# lora_external_dev_board.net
KiCad netlist of a schematic drawn in EasyEDA
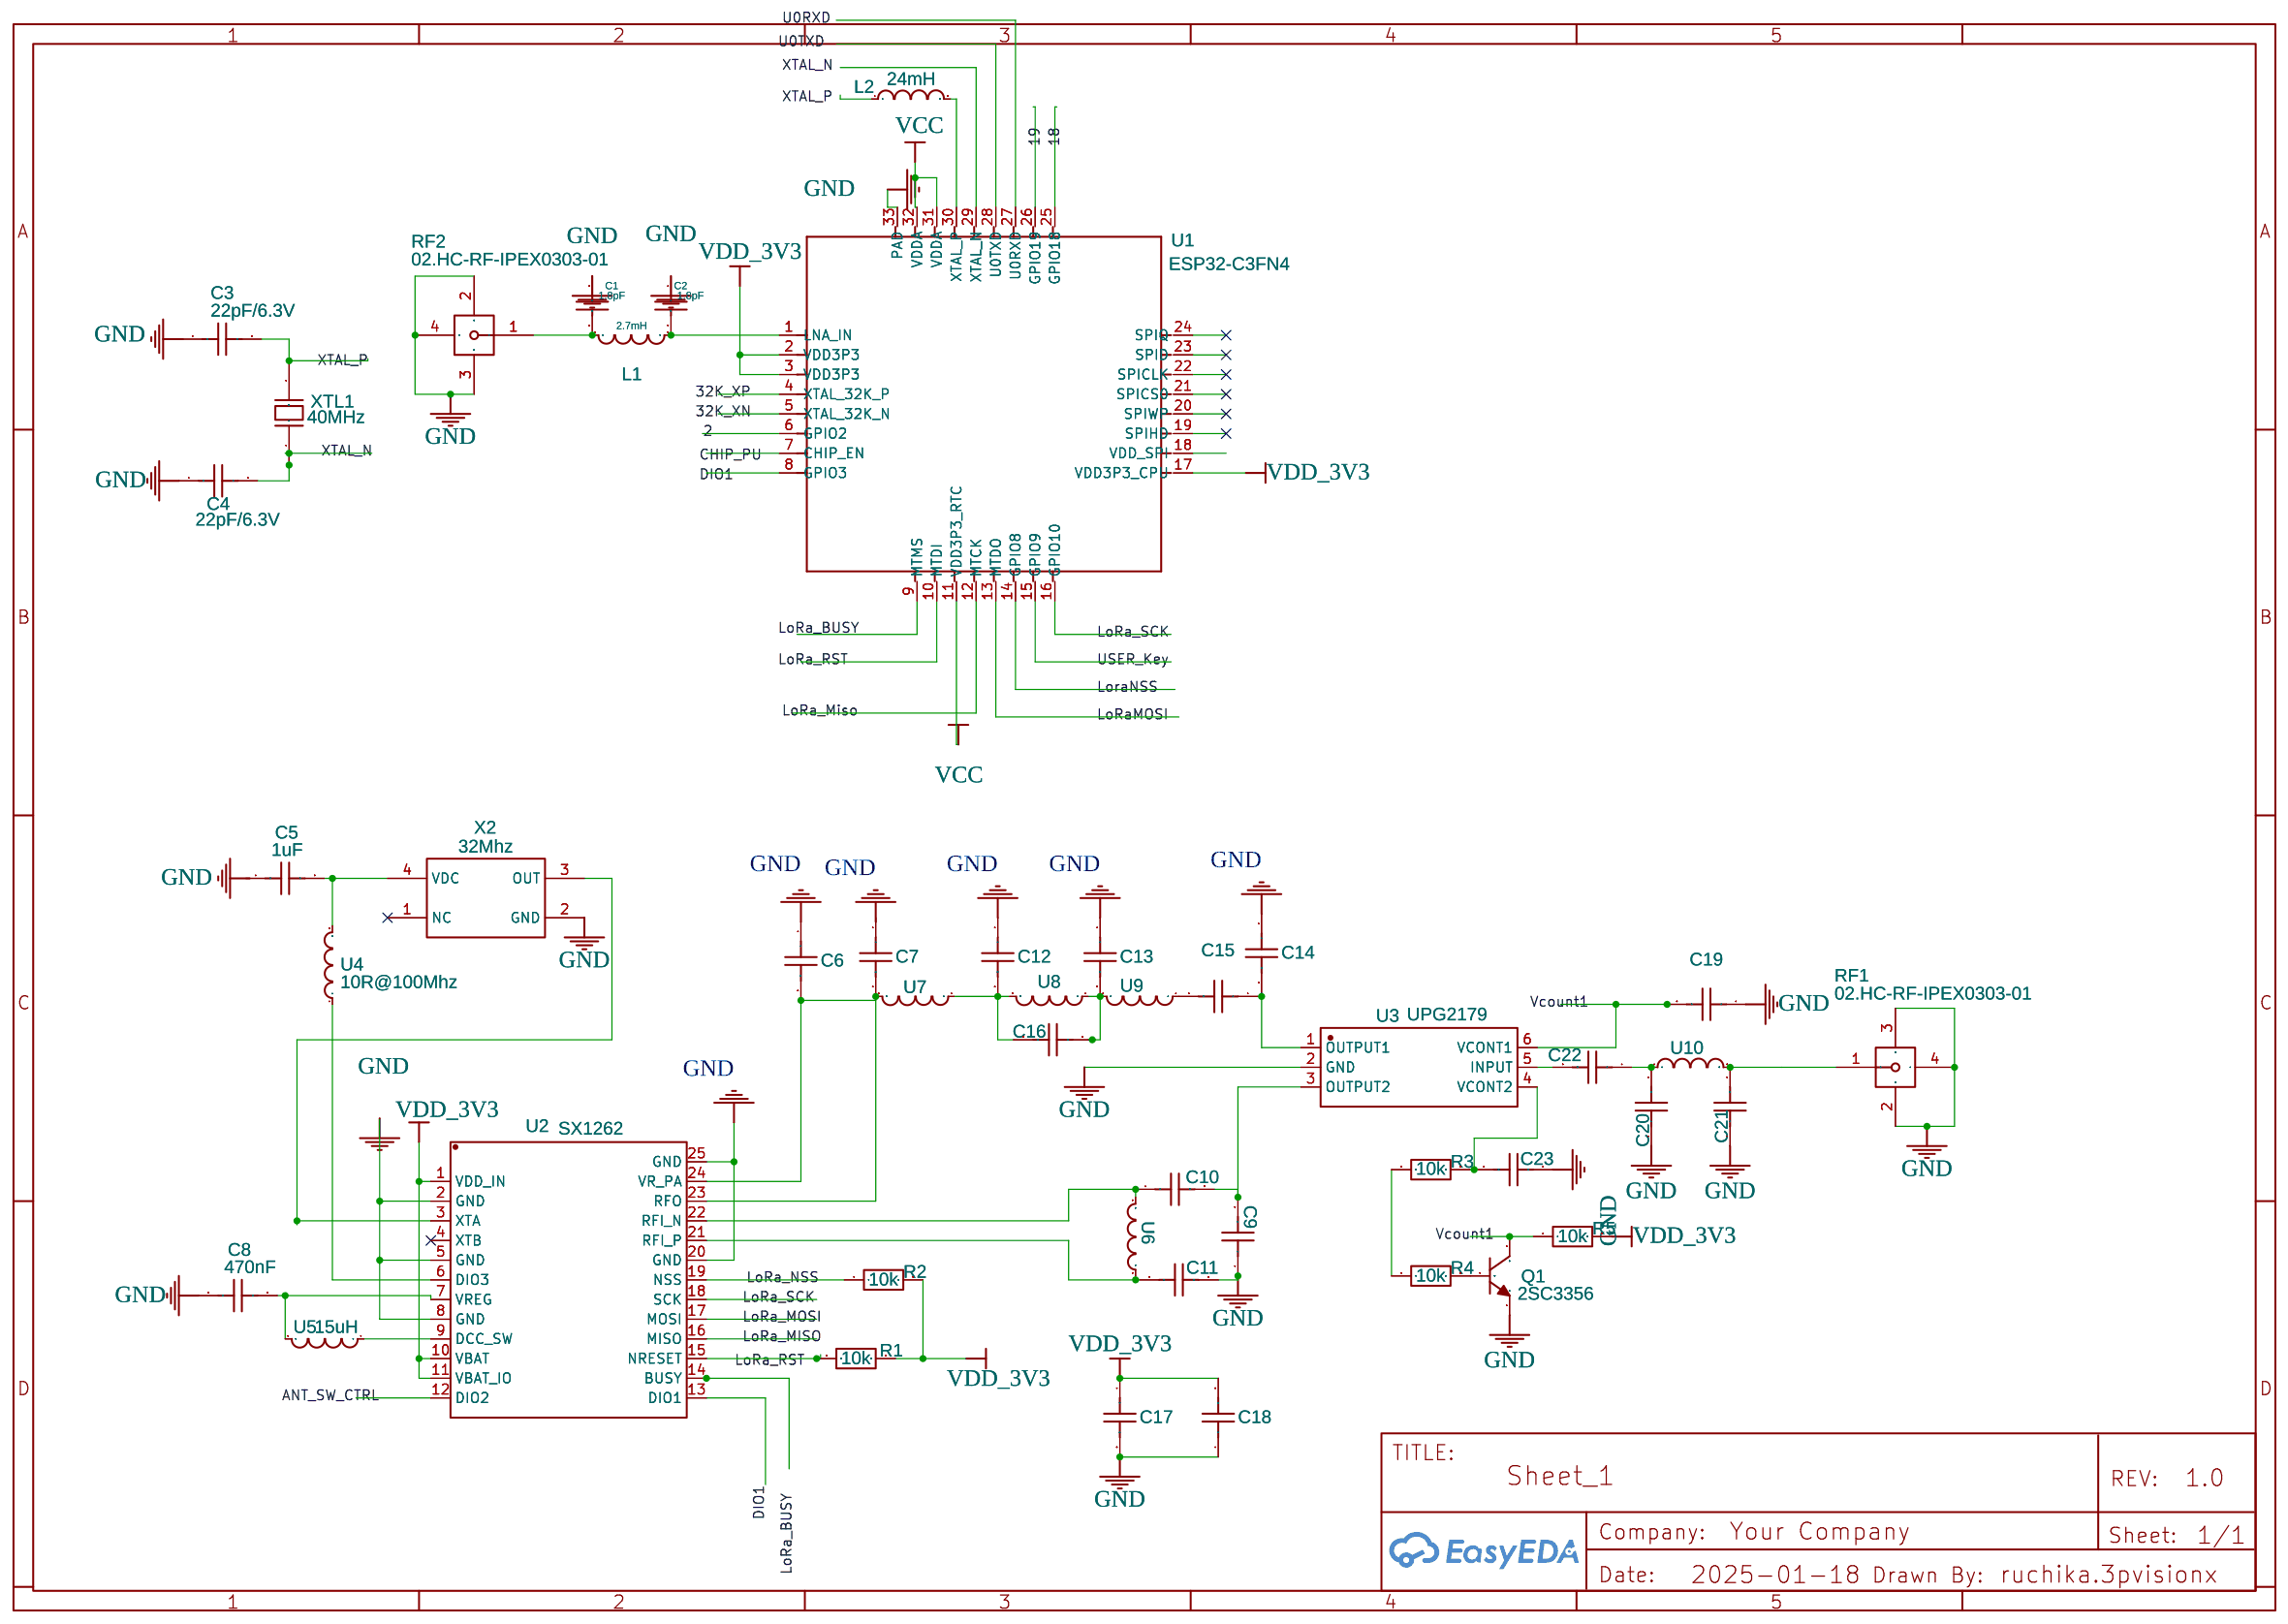
[diagram p0: schematic sheet]

(export (version "E")
  (design (tool "Eeschema 10.0.6"))
  (components
    (comp (ref "C1")
      (value "1.8pF")
      (fields
        (field (name "Manufacturer Part") "GJM1555C1H1R8BB01D")
        (field (name "Manufacturer") "muRata(村田)")
      )
      (libsource (lib "") (part "GJM1555C1H1R8BB01D"))
    )
    (comp (ref "C2")
      (value "1.8pF")
      (fields
        (field (name "Manufacturer Part") "GJM1555C1H1R8BB01D")
        (field (name "Manufacturer") "muRata(村田)")
      )
      (libsource (lib "") (part "GJM1555C1H1R8BB01D"))
    )
    (comp (ref "C3")
      (value "22pF/6.3V")
      (fields (field (name "Manufacturer Part") "22pF/6.3V(10%)-0402"))
      (libsource (lib "") (part "22PF/6.3V(10%)-0402"))
    )
    (comp (ref "C4")
      (value "22pF/6.3V")
      (fields (field (name "Manufacturer Part") "22pF/6.3V(10%)-0402"))
      (libsource (lib "") (part "22PF/6.3V(10%)-0402"))
    )
    (comp (ref "C5")
      (value "1uF")
      (fields
        (field (name "Manufacturer Part") "1uf/250V/CBBCapacitor")
        (field (name "Manufacturer") "ReliaPro")
      )
      (libsource (lib "") (part "1uf/250V/CBBCapacitor_2"))
    )
    (comp (ref "C6")
      (value "1uF")
      (fields
        (field (name "Manufacturer Part") "1uf/250V/CBBCapacitor")
        (field (name "Manufacturer") "ReliaPro")
      )
      (libsource (lib "") (part "1uf/250V/CBBCapacitor"))
    )
    (comp (ref "C7")
      (value "1uF")
      (fields
        (field (name "Manufacturer Part") "1uf/250V/CBBCapacitor")
        (field (name "Manufacturer") "ReliaPro")
      )
      (libsource (lib "") (part "1uf/250V/CBBCapacitor"))
    )
    (comp (ref "C8")
      (value "470nF")
      (fields
        (field (name "Manufacturer Part") "1uf/250V/CBBCapacitor")
        (field (name "Manufacturer") "ReliaPro")
      )
      (libsource (lib "") (part "1uf/250V/CBBCapacitor_2"))
    )
    (comp (ref "C9")
      (value "1uF")
      (fields
        (field (name "Manufacturer Part") "1uf/250V/CBBCapacitor")
        (field (name "Manufacturer") "ReliaPro")
      )
      (libsource (lib "") (part "1uf/250V/CBBCapacitor_1"))
    )
    (comp (ref "C10")
      (value "1uF")
      (fields
        (field (name "Manufacturer Part") "1uf/250V/CBBCapacitor")
        (field (name "Manufacturer") "ReliaPro")
      )
      (libsource (lib "") (part "1uf/250V/CBBCapacitor_2"))
    )
    (comp (ref "C11")
      (value "1uF")
      (fields
        (field (name "Manufacturer Part") "1uf/250V/CBBCapacitor")
        (field (name "Manufacturer") "ReliaPro")
      )
      (libsource (lib "") (part "1uf/250V/CBBCapacitor_2"))
    )
    (comp (ref "C12")
      (value "1uF")
      (fields
        (field (name "Manufacturer Part") "1uf/250V/CBBCapacitor")
        (field (name "Manufacturer") "ReliaPro")
      )
      (libsource (lib "") (part "1uf/250V/CBBCapacitor"))
    )
    (comp (ref "C13")
      (value "1uF")
      (fields
        (field (name "Manufacturer Part") "1uf/250V/CBBCapacitor")
        (field (name "Manufacturer") "ReliaPro")
      )
      (libsource (lib "") (part "1uf/250V/CBBCapacitor"))
    )
    (comp (ref "C14")
      (value "1uF")
      (fields
        (field (name "Manufacturer Part") "1uf/250V/CBBCapacitor")
        (field (name "Manufacturer") "ReliaPro")
      )
      (libsource (lib "") (part "1uf/250V/CBBCapacitor"))
    )
    (comp (ref "C15")
      (value "1uF")
      (fields
        (field (name "Manufacturer Part") "1uf/250V/CBBCapacitor")
        (field (name "Manufacturer") "ReliaPro")
      )
      (libsource (lib "") (part "1uf/250V/CBBCapacitor_3"))
    )
    (comp (ref "C16")
      (value "1uF")
      (fields
        (field (name "Manufacturer Part") "1uf/250V/CBBCapacitor")
        (field (name "Manufacturer") "ReliaPro")
      )
      (libsource (lib "") (part "1uf/250V/CBBCapacitor_3"))
    )
    (comp (ref "C17")
      (value "1uF")
      (fields
        (field (name "Manufacturer Part") "1uf/250V/CBBCapacitor")
        (field (name "Manufacturer") "ReliaPro")
      )
      (libsource (lib "") (part "1uf/250V/CBBCapacitor"))
    )
    (comp (ref "C18")
      (value "1uF")
      (fields
        (field (name "Manufacturer Part") "1uf/250V/CBBCapacitor")
        (field (name "Manufacturer") "ReliaPro")
      )
      (libsource (lib "") (part "1uf/250V/CBBCapacitor_1"))
    )
    (comp (ref "C19")
      (value "1uF")
      (fields
        (field (name "Manufacturer Part") "1uf/250V/CBBCapacitor")
        (field (name "Manufacturer") "ReliaPro")
      )
      (libsource (lib "") (part "1uf/250V/CBBCapacitor_3"))
    )
    (comp (ref "C20")
      (value "1uF")
      (fields
        (field (name "Manufacturer Part") "1uf/250V/CBBCapacitor")
        (field (name "Manufacturer") "ReliaPro")
      )
      (libsource (lib "") (part "1uf/250V/CBBCapacitor_1"))
    )
    (comp (ref "C21")
      (value "1uF")
      (fields
        (field (name "Manufacturer Part") "1uf/250V/CBBCapacitor")
        (field (name "Manufacturer") "ReliaPro")
      )
      (libsource (lib "") (part "1uf/250V/CBBCapacitor_1"))
    )
    (comp (ref "C22")
      (value "1uF")
      (fields
        (field (name "Manufacturer Part") "1uf/250V/CBBCapacitor")
        (field (name "Manufacturer") "ReliaPro")
      )
      (libsource (lib "") (part "1uf/250V/CBBCapacitor_3"))
    )
    (comp (ref "C23")
      (value "1uF")
      (fields
        (field (name "Manufacturer Part") "1uf/250V/CBBCapacitor")
        (field (name "Manufacturer") "ReliaPro")
      )
      (libsource (lib "") (part "1uf/250V/CBBCapacitor_3"))
    )
    (comp (ref "L1") (value "2.7mH") (libsource (lib "") (part "2.7mH sb3m")))
    (comp (ref "L2")
      (value "24mH")
      (fields (field (name "Manufacturer") "ML"))
      (libsource (lib "") (part "Inductor TH"))
    )
    (comp (ref "Q1")
      (value "2SC3356")
      (fields (field (name "Manufacturer") "FOSAN(富信)"))
      (libsource (lib "") (part "2SC3356_C5119709"))
    )
    (comp (ref "R1")
      (value "10k")
      (fields (field (name "Manufacturer Part") "贴片电阻ChipResistors"))
      (libsource (lib "") (part "贴片电阻CHIPRESISTORS"))
    )
    (comp (ref "R2")
      (value "10k")
      (fields (field (name "Manufacturer Part") "贴片电阻ChipResistors"))
      (libsource (lib "") (part "贴片电阻CHIPRESISTORS"))
    )
    (comp (ref "R3")
      (value "10k")
      (fields (field (name "Manufacturer Part") "贴片电阻ChipResistors"))
      (libsource (lib "") (part "贴片电阻CHIPRESISTORS"))
    )
    (comp (ref "R4")
      (value "10k")
      (fields (field (name "Manufacturer Part") "贴片电阻ChipResistors"))
      (libsource (lib "") (part "贴片电阻CHIPRESISTORS"))
    )
    (comp (ref "R5")
      (value "10k")
      (fields (field (name "Manufacturer Part") "贴片电阻ChipResistors"))
      (libsource (lib "") (part "贴片电阻CHIPRESISTORS"))
    )
    (comp (ref "RF1")
      (value "02.HC-RF-IPEX0303-01")
      (fields
        (field (name "Manufacturer Part") "HC-RF-IPEX0303-01")
        (field (name "Manufacturer") "HCTL(华灿天禄)")
      )
      (libsource (lib "") (part "02.HC-RF-IPEX0303-01"))
    )
    (comp (ref "RF2")
      (value "02.HC-RF-IPEX0303-01")
      (fields
        (field (name "Manufacturer Part") "HC-RF-IPEX0303-01")
        (field (name "Manufacturer") "HCTL(华灿天禄)")
      )
      (libsource (lib "") (part "02.HC-RF-IPEX0303-01_1"))
    )
    (comp (ref "U1") (value "ESP32-C3FN4") (libsource (lib "") (part "ESP32-C3FN4")))
    (comp (ref "U2")
      (value "SX1262")
      (fields (field (name "Manufacturer Part") "SX1262IMLTRT") (field (name "Manufacturer") "SEMTECH"))
      (libsource (lib "") (part "SX1262IMLTRT"))
    )
    (comp (ref "U3")
      (value "UPG2179")
      (fields
        (field (name "Manufacturer Part") "UPG2179TB-E4-A")
        (field (name "Manufacturer") "RENESAS(瑞萨)/IDT")
      )
      (libsource (lib "") (part "UPG2179TB-E4-A"))
    )
    (comp (ref "U4")
      (value "10R@100Mhz")
      (fields (field (name "Manufacturer Part") "10uH-INDUCTOR-0603"))
      (libsource (lib "") (part "10UH-INDUCTOR-0603_4"))
    )
    (comp (ref "U5")
      (value "15uH")
      (fields (field (name "Manufacturer Part") "10uH-INDUCTOR-0603"))
      (libsource (lib "") (part "10UH-INDUCTOR-0603_5"))
    )
    (comp (ref "U6")
      (value "15uH")
      (fields (field (name "Manufacturer Part") "10uH-INDUCTOR-0603"))
      (libsource (lib "") (part "10UH-INDUCTOR-0603_3"))
    )
    (comp (ref "U7")
      (value "15uH")
      (fields (field (name "Manufacturer Part") "10uH-INDUCTOR-0603"))
      (libsource (lib "") (part "10UH-INDUCTOR-0603"))
    )
    (comp (ref "U8")
      (value "15uH")
      (fields (field (name "Manufacturer Part") "10uH-INDUCTOR-0603"))
      (libsource (lib "") (part "10UH-INDUCTOR-0603"))
    )
    (comp (ref "U9")
      (value "15uH")
      (fields (field (name "Manufacturer Part") "10uH-INDUCTOR-0603"))
      (libsource (lib "") (part "10UH-INDUCTOR-0603_1"))
    )
    (comp (ref "U10")
      (value "15uH")
      (fields (field (name "Manufacturer Part") "10uH-INDUCTOR-0603"))
      (libsource (lib "") (part "10UH-INDUCTOR-0603_2"))
    )
    (comp (ref "X2")
      (value "32Mhz")
      (fields (field (name "Manufacturer") "YIC"))
      (libsource (lib "") (part "OSC40M-3.3/S5"))
    )
    (comp (ref "XTL1")
      (value "40MHz")
      (fields (field (name "Manufacturer Part") "NTPL INSIDE"))
      (libsource (lib "") (part "XTL - 16MHZ"))
    )
  )
  (nets
    (net (code "1") (name "/2") (class "Default")
      (node (ref "U1") (pin "6") (pinfunction "GPIO2_6") (pintype "unspecified"))
    )
    (net (code "9") (name "/LoRaMOSI") (class "Default")
      (node (ref "U1") (pin "13") (pinfunction "MTDO_13") (pintype "unspecified"))
    )
    (net (code "11") (name "/LoRa_MISO") (class "Default")
      (node (ref "U2") (pin "16") (pinfunction "MISO_16") (pintype "unspecified"))
    )
    (net (code "12") (name "/LoRa_MOSI") (class "Default")
      (node (ref "U2") (pin "17") (pinfunction "MOSI_17") (pintype "unspecified"))
    )
    (net (code "14") (name "/LoRa_NSS") (class "Default")
      (node (ref "R2") (pin "1") (pinfunction "1_1") (pintype "unspecified"))
      (node (ref "U2") (pin "19") (pinfunction "NSS_19") (pintype "unspecified"))
    )
    (net (code "16") (name "/LoRa_SCK") (class "Default")
      (node (ref "U1") (pin "16") (pinfunction "GPIO10_16") (pintype "unspecified"))
      (node (ref "U2") (pin "18") (pinfunction "SCK_18") (pintype "unspecified"))
    )
    (net (code "17") (name "/LoraNSS") (class "Default")
      (node (ref "U1") (pin "14") (pinfunction "GPIO8_14") (pintype "unspecified"))
    )
    (net (code "20") (name "/USER_Key") (class "Default")
      (node (ref "U1") (pin "15") (pinfunction "GPIO9_15") (pintype "unspecified"))
    )
    (net (code "22") (name "/XTAL_N") (class "Default")
      (node (ref "C4") (pin "2") (pinfunction "2_2") (pintype "unspecified"))
      (node (ref "XTL1") (pin "1") (pinfunction "1_1") (pintype "unspecified"))
    )
    (net (code "24") (name "GND") (class "Default")
      (node (ref "C1") (pin "1") (pinfunction "1_1") (pintype "input"))
      (node (ref "C11") (pin "2") (pinfunction "2_2") (pintype "unspecified"))
      (node (ref "C12") (pin "1") (pinfunction "1_1") (pintype "unspecified"))
      (node (ref "C13") (pin "1") (pinfunction "1_1") (pintype "unspecified"))
      (node (ref "C14") (pin "1") (pinfunction "1_1") (pintype "unspecified"))
      (node (ref "C17") (pin "2") (pinfunction "2_2") (pintype "unspecified"))
      (node (ref "C18") (pin "1") (pinfunction "1_1") (pintype "unspecified"))
      (node (ref "C19") (pin "1") (pinfunction "1_1") (pintype "unspecified"))
      (node (ref "C2") (pin "1") (pinfunction "1_1") (pintype "input"))
      (node (ref "C20") (pin "1") (pinfunction "1_1") (pintype "unspecified"))
      (node (ref "C21") (pin "1") (pinfunction "1_1") (pintype "unspecified"))
      (node (ref "C23") (pin "1") (pinfunction "1_1") (pintype "unspecified"))
      (node (ref "C3") (pin "1") (pinfunction "1_1") (pintype "unspecified"))
      (node (ref "C4") (pin "1") (pinfunction "1_1") (pintype "unspecified"))
      (node (ref "C6") (pin "1") (pinfunction "1_1") (pintype "unspecified"))
      (node (ref "C8") (pin "1") (pinfunction "1_1") (pintype "unspecified"))
      (node (ref "C9") (pin "1") (pinfunction "1_1") (pintype "unspecified"))
      (node (ref "Q1") (pin "1") (pinfunction "E_1") (pintype "input"))
      (node (ref "RF1") (pin "2") (pinfunction "2_2") (pintype "unspecified"))
      (node (ref "RF1") (pin "3") (pinfunction "3_3") (pintype "unspecified"))
      (node (ref "RF1") (pin "4") (pinfunction "4_4") (pintype "unspecified"))
      (node (ref "RF2") (pin "2") (pinfunction "2_2") (pintype "unspecified"))
      (node (ref "RF2") (pin "3") (pinfunction "3_3") (pintype "unspecified"))
      (node (ref "RF2") (pin "4") (pinfunction "4_4") (pintype "unspecified"))
      (node (ref "U1") (pin "33") (pinfunction "PAD_33") (pintype "unspecified"))
      (node (ref "U2") (pin "2") (pinfunction "GND_2") (pintype "unspecified"))
      (node (ref "U2") (pin "20") (pinfunction "GND_20") (pintype "unspecified"))
      (node (ref "U2") (pin "25") (pinfunction "GND_25") (pintype "unspecified"))
      (node (ref "U2") (pin "5") (pinfunction "GND_5") (pintype "unspecified"))
      (node (ref "U2") (pin "8") (pinfunction "GND_8") (pintype "unspecified"))
      (node (ref "U3") (pin "2") (pinfunction "GND_2") (pintype "unspecified"))
      (node (ref "X2") (pin "2") (pinfunction "GND_2") (pintype "unspecified"))
    )
    (net (code "25") (name "Net-(C1-Pad2)") (class "Default")
      (node (ref "C1") (pin "2") (pinfunction "2_2") (pintype "input"))
      (node (ref "L1") (pin "1") (pinfunction "1_1") (pintype "unspecified"))
      (node (ref "RF2") (pin "1") (pinfunction "1_1") (pintype "unspecified"))
    )
    (net (code "26") (name "Net-(C3-Pad2)") (class "Default")
      (node (ref "C3") (pin "2") (pinfunction "2_2") (pintype "unspecified"))
      (node (ref "XTL1") (pin "2") (pinfunction "2_2") (pintype "unspecified"))
    )
    (net (code "27") (name "Net-(C12-Pad2)") (class "Default")
      (node (ref "C12") (pin "2") (pinfunction "2_2") (pintype "unspecified"))
      (node (ref "C16") (pin "2") (pinfunction "2_2") (pintype "unspecified"))
      (node (ref "U7") (pin "1") (pinfunction "1_1") (pintype "unspecified"))
      (node (ref "U8") (pin "2") (pinfunction "2_2") (pintype "unspecified"))
    )
    (net (code "28") (name "Net-(C13-Pad2)") (class "Default")
      (node (ref "C13") (pin "2") (pinfunction "2_2") (pintype "unspecified"))
      (node (ref "C16") (pin "1") (pinfunction "1_1") (pintype "unspecified"))
      (node (ref "U8") (pin "1") (pinfunction "1_1") (pintype "unspecified"))
      (node (ref "U9") (pin "2") (pinfunction "2_2") (pintype "unspecified"))
    )
    (net (code "29") (name "Net-(C15-Pad2)") (class "Default")
      (node (ref "C15") (pin "2") (pinfunction "2_2") (pintype "unspecified"))
      (node (ref "U9") (pin "1") (pinfunction "1_1") (pintype "unspecified"))
    )
    (net (code "30") (name "Net-(C20-Pad2)") (class "Default")
      (node (ref "C20") (pin "2") (pinfunction "2_2") (pintype "unspecified"))
      (node (ref "C22") (pin "1") (pinfunction "1_1") (pintype "unspecified"))
      (node (ref "U10") (pin "1") (pinfunction "1_1") (pintype "unspecified"))
    )
    (net (code "31") (name "Net-(C21-Pad2)") (class "Default")
      (node (ref "C21") (pin "2") (pinfunction "2_2") (pintype "unspecified"))
      (node (ref "RF1") (pin "1") (pinfunction "1_1") (pintype "unspecified"))
      (node (ref "U10") (pin "2") (pinfunction "2_2") (pintype "unspecified"))
    )
    (net (code "32") (name "Net-(Q1-B)") (class "Default")
      (node (ref "Q1") (pin "2") (pinfunction "B_2") (pintype "input"))
      (node (ref "R4") (pin "2") (pinfunction "2_2") (pintype "unspecified"))
    )
    (net (code "33") (name "Net-(Q1-C)") (class "Default")
      (node (ref "Q1") (pin "3") (pinfunction "C_3") (pintype "input"))
      (node (ref "R5") (pin "1") (pinfunction "1_1") (pintype "unspecified"))
    )
    (net (code "34") (name "Net-(R3-Pad1)") (class "Default")
      (node (ref "R3") (pin "1") (pinfunction "1_1") (pintype "unspecified"))
      (node (ref "R4") (pin "1") (pinfunction "1_1") (pintype "unspecified"))
    )
    (net (code "35") (name "Net-(U1-LNA_IN)") (class "Default")
      (node (ref "C2") (pin "2") (pinfunction "2_2") (pintype "input"))
      (node (ref "L1") (pin "2") (pinfunction "2_2") (pintype "unspecified"))
      (node (ref "U1") (pin "1") (pinfunction "LNA_IN_1") (pintype "unspecified"))
    )
    (net (code "36") (name "Net-(U1-XTAL_P)") (class "Default")
      (node (ref "L2") (pin "2") (pinfunction "2_2") (pintype "unspecified"))
      (node (ref "U1") (pin "30") (pinfunction "XTAL_P_30") (pintype "unspecified"))
    )
    (net (code "37") (name "Net-(U2-DCC_SW)") (class "Default")
      (node (ref "U2") (pin "9") (pinfunction "DCC_SW_9") (pintype "unspecified"))
      (node (ref "U5") (pin "1") (pinfunction "1_1") (pintype "unspecified"))
    )
    (net (code "38") (name "Net-(U2-DIO3)") (class "Default")
      (node (ref "U2") (pin "6") (pinfunction "DIO3_6") (pintype "unspecified"))
      (node (ref "U4") (pin "1") (pinfunction "1_1") (pintype "unspecified"))
    )
    (net (code "39") (name "Net-(U2-NRESET)") (class "Default")
      (node (ref "R1") (pin "1") (pinfunction "1_1") (pintype "unspecified"))
      (node (ref "U2") (pin "15") (pinfunction "NRESET_15") (pintype "unspecified"))
    )
    (net (code "40") (name "Net-(U2-RFI_N)") (class "Default")
      (node (ref "C10") (pin "1") (pinfunction "1_1") (pintype "unspecified"))
      (node (ref "U2") (pin "22") (pinfunction "RFI_N_22") (pintype "unspecified"))
      (node (ref "U6") (pin "2") (pinfunction "2_2") (pintype "unspecified"))
    )
    (net (code "41") (name "Net-(U2-RFI_P)") (class "Default")
      (node (ref "C11") (pin "1") (pinfunction "1_1") (pintype "unspecified"))
      (node (ref "U2") (pin "21") (pinfunction "RFI_P_21") (pintype "unspecified"))
      (node (ref "U6") (pin "1") (pinfunction "1_1") (pintype "unspecified"))
    )
    (net (code "42") (name "Net-(U2-RFO)") (class "Default")
      (node (ref "C6") (pin "2") (pinfunction "2_2") (pintype "unspecified"))
      (node (ref "C7") (pin "2") (pinfunction "2_2") (pintype "unspecified"))
      (node (ref "U2") (pin "23") (pinfunction "RFO_23") (pintype "unspecified"))
      (node (ref "U2") (pin "24") (pinfunction "VR_PA_24") (pintype "unspecified"))
      (node (ref "U7") (pin "2") (pinfunction "2_2") (pintype "unspecified"))
    )
    (net (code "43") (name "Net-(U2-VREG)") (class "Default")
      (node (ref "C8") (pin "2") (pinfunction "2_2") (pintype "unspecified"))
      (node (ref "U2") (pin "7") (pinfunction "VREG_7") (pintype "unspecified"))
      (node (ref "U5") (pin "2") (pinfunction "2_2") (pintype "unspecified"))
    )
    (net (code "44") (name "Net-(U2-XTA)") (class "Default")
      (node (ref "U2") (pin "3") (pinfunction "XTA_3") (pintype "unspecified"))
      (node (ref "X2") (pin "3") (pinfunction "OUT_3") (pintype "unspecified"))
    )
    (net (code "45") (name "Net-(U3-INPUT)") (class "Default")
      (node (ref "C22") (pin "2") (pinfunction "2_2") (pintype "unspecified"))
      (node (ref "U3") (pin "5") (pinfunction "INPUT_5") (pintype "unspecified"))
    )
    (net (code "46") (name "Net-(U3-OUTPUT1)") (class "Default")
      (node (ref "C14") (pin "2") (pinfunction "2_2") (pintype "unspecified"))
      (node (ref "C15") (pin "1") (pinfunction "1_1") (pintype "unspecified"))
      (node (ref "U3") (pin "1") (pinfunction "OUTPUT1_1") (pintype "unspecified"))
    )
    (net (code "47") (name "Net-(U3-OUTPUT2)") (class "Default")
      (node (ref "C10") (pin "2") (pinfunction "2_2") (pintype "unspecified"))
      (node (ref "C9") (pin "2") (pinfunction "2_2") (pintype "unspecified"))
      (node (ref "U3") (pin "3") (pinfunction "OUTPUT2_3") (pintype "unspecified"))
    )
    (net (code "48") (name "Net-(U3-VCONT1)") (class "Default")
      (node (ref "C19") (pin "2") (pinfunction "2_2") (pintype "unspecified"))
      (node (ref "U3") (pin "6") (pinfunction "VCONT1_6") (pintype "unspecified"))
    )
    (net (code "49") (name "Net-(U3-VCONT2)") (class "Default")
      (node (ref "C23") (pin "2") (pinfunction "2_2") (pintype "unspecified"))
      (node (ref "R3") (pin "2") (pinfunction "2_2") (pintype "unspecified"))
      (node (ref "U3") (pin "4") (pinfunction "VCONT2_4") (pintype "unspecified"))
    )
    (net (code "50") (name "Net-(X2-VDC)") (class "Default")
      (node (ref "C5") (pin "2") (pinfunction "2_2") (pintype "unspecified"))
      (node (ref "U4") (pin "2") (pinfunction "2_2") (pintype "unspecified"))
      (node (ref "X2") (pin "4") (pinfunction "VDC_4") (pintype "unspecified"))
    )
    (net (code "51") (name "VCC") (class "Default")
      (node (ref "U1") (pin "11") (pinfunction "VDD3P3_RTC_11") (pintype "unspecified"))
      (node (ref "U1") (pin "31") (pinfunction "VDDA_31") (pintype "unspecified"))
      (node (ref "U1") (pin "32") (pinfunction "VDDA_32") (pintype "unspecified"))
    )
    (net (code "52") (name "VDD_3V3") (class "Default")
      (node (ref "C17") (pin "1") (pinfunction "1_1") (pintype "unspecified"))
      (node (ref "C18") (pin "2") (pinfunction "2_2") (pintype "unspecified"))
      (node (ref "R1") (pin "2") (pinfunction "2_2") (pintype "unspecified"))
      (node (ref "R2") (pin "2") (pinfunction "2_2") (pintype "unspecified"))
      (node (ref "R5") (pin "2") (pinfunction "2_2") (pintype "unspecified"))
      (node (ref "U1") (pin "17") (pinfunction "VDD3P3_CPU_17") (pintype "unspecified"))
      (node (ref "U1") (pin "2") (pinfunction "VDD3P3_2") (pintype "unspecified"))
      (node (ref "U1") (pin "3") (pinfunction "VDD3P3_3") (pintype "unspecified"))
      (node (ref "U2") (pin "1") (pinfunction "VDD_IN_1") (pintype "unspecified"))
      (node (ref "U2") (pin "10") (pinfunction "VBAT_10") (pintype "unspecified"))
      (node (ref "U2") (pin "11") (pinfunction "VBAT_IO_11") (pintype "unspecified"))
    )
    (net (code "53") (name "unconnected-(C5-Pad1)") (class "Default")
      (node (ref "C5") (pin "1") (pinfunction "1_1") (pintype "unspecified"))
    )
    (net (code "54") (name "unconnected-(C7-Pad1)") (class "Default")
      (node (ref "C7") (pin "1") (pinfunction "1_1") (pintype "unspecified"))
    )
    (net (code "55") (name "unconnected-(L2-Pad1)") (class "Default")
      (node (ref "L2") (pin "1") (pinfunction "1_1") (pintype "unspecified"))
    )
    (net (code "56") (name "unconnected-(U1-CHIP_EN-Pad7)") (class "Default")
      (node (ref "U1") (pin "7") (pinfunction "CHIP_EN_7") (pintype "unspecified"))
    )
    (net (code "57") (name "unconnected-(U1-GPIO3-Pad8)") (class "Default")
      (node (ref "U1") (pin "8") (pinfunction "GPIO3_8") (pintype "unspecified"))
    )
    (net (code "58") (name "unconnected-(U1-GPIO18-Pad25)") (class "Default")
      (node (ref "U1") (pin "25") (pinfunction "GPIO18_25") (pintype "unspecified"))
    )
    (net (code "59") (name "unconnected-(U1-GPIO19-Pad26)") (class "Default")
      (node (ref "U1") (pin "26") (pinfunction "GPIO19_26") (pintype "unspecified"))
    )
    (net (code "60") (name "unconnected-(U1-MTCK-Pad12)") (class "Default")
      (node (ref "U1") (pin "12") (pinfunction "MTCK_12") (pintype "unspecified"))
    )
    (net (code "61") (name "unconnected-(U1-MTDI-Pad10)") (class "Default")
      (node (ref "U1") (pin "10") (pinfunction "MTDI_10") (pintype "unspecified"))
    )
    (net (code "62") (name "unconnected-(U1-MTMS-Pad9)") (class "Default")
      (node (ref "U1") (pin "9") (pinfunction "MTMS_9") (pintype "unspecified"))
    )
    (net (code "63") (name "unconnected-(U1-SPICLK-Pad22)") (class "Default")
      (node (ref "U1") (pin "22") (pinfunction "SPICLK_22") (pintype "unspecified+no_connect"))
    )
    (net (code "64") (name "unconnected-(U1-SPICS0-Pad21)") (class "Default")
      (node (ref "U1") (pin "21") (pinfunction "SPICS0_21") (pintype "unspecified+no_connect"))
    )
    (net (code "65") (name "unconnected-(U1-SPID-Pad23)") (class "Default")
      (node (ref "U1") (pin "23") (pinfunction "SPID_23") (pintype "unspecified+no_connect"))
    )
    (net (code "66") (name "unconnected-(U1-SPIHD-Pad19)") (class "Default")
      (node (ref "U1") (pin "19") (pinfunction "SPIHD_19") (pintype "unspecified+no_connect"))
    )
    (net (code "67") (name "unconnected-(U1-SPIQ-Pad24)") (class "Default")
      (node (ref "U1") (pin "24") (pinfunction "SPIQ_24") (pintype "unspecified+no_connect"))
    )
    (net (code "68") (name "unconnected-(U1-SPIWP-Pad20)") (class "Default")
      (node (ref "U1") (pin "20") (pinfunction "SPIWP_20") (pintype "unspecified+no_connect"))
    )
    (net (code "69") (name "unconnected-(U1-U0RXD-Pad27)") (class "Default")
      (node (ref "U1") (pin "27") (pinfunction "U0RXD_27") (pintype "unspecified"))
    )
    (net (code "70") (name "unconnected-(U1-U0TXD-Pad28)") (class "Default")
      (node (ref "U1") (pin "28") (pinfunction "U0TXD_28") (pintype "unspecified"))
    )
    (net (code "71") (name "unconnected-(U1-VDD_SPI-Pad18)") (class "Default")
      (node (ref "U1") (pin "18") (pinfunction "VDD_SPI_18") (pintype "unspecified"))
    )
    (net (code "72") (name "unconnected-(U1-XTAL_32K_N-Pad5)") (class "Default")
      (node (ref "U1") (pin "5") (pinfunction "XTAL_32K_N_5") (pintype "unspecified"))
    )
    (net (code "73") (name "unconnected-(U1-XTAL_32K_P-Pad4)") (class "Default")
      (node (ref "U1") (pin "4") (pinfunction "XTAL_32K_P_4") (pintype "unspecified"))
    )
    (net (code "74") (name "unconnected-(U1-XTAL_N-Pad29)") (class "Default")
      (node (ref "U1") (pin "29") (pinfunction "XTAL_N_29") (pintype "unspecified"))
    )
    (net (code "75") (name "unconnected-(U2-BUSY-Pad14)") (class "Default")
      (node (ref "U2") (pin "14") (pinfunction "BUSY_14") (pintype "unspecified"))
    )
    (net (code "76") (name "unconnected-(U2-DIO1-Pad13)") (class "Default")
      (node (ref "U2") (pin "13") (pinfunction "DIO1_13") (pintype "unspecified"))
    )
    (net (code "77") (name "unconnected-(U2-DIO2-Pad12)") (class "Default")
      (node (ref "U2") (pin "12") (pinfunction "DIO2_12") (pintype "unspecified"))
    )
    (net (code "78") (name "unconnected-(U2-XTB-Pad4)") (class "Default")
      (node (ref "U2") (pin "4") (pinfunction "XTB_4") (pintype "unspecified+no_connect"))
    )
    (net (code "79") (name "unconnected-(X2-NC-Pad1)") (class "Default")
      (node (ref "X2") (pin "1") (pinfunction "NC_1") (pintype "unspecified+no_connect"))
    )
  )
)
